# Sheet1.net
KiCad netlist of a schematic drawn in Altium Designer
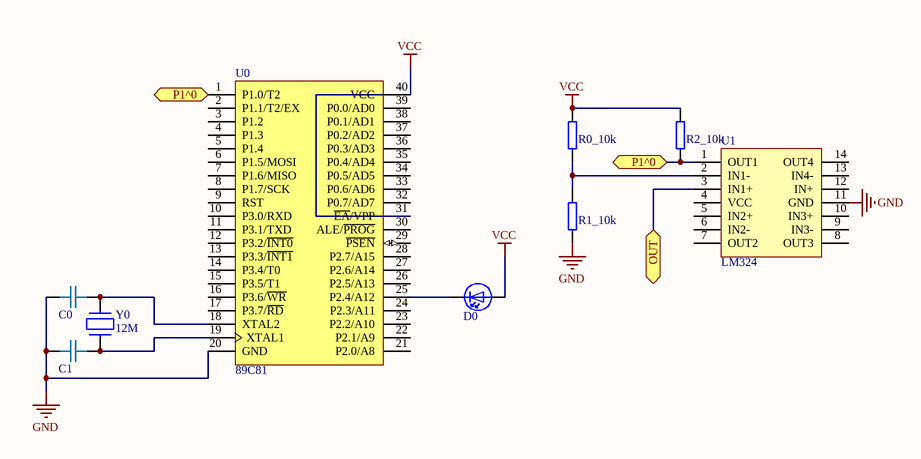
[diagram p0: Sheet1.SchDoc]

(export (version "E")
  (design (tool "Eeschema 10.0.6"))
  (components
    (comp (ref "C0") (value "22pf") (footprint "capacitor-0.1") (libsource (lib "单片机常用原件库") (part "C_1")))
    (comp (ref "C1") (value "C_1") (footprint "capacitor-0.1") (libsource (lib "单片机常用原件库") (part "C_1")))
    (comp (ref "D0") (value "LED") (footprint "led-3") (libsource (lib "单片机常用原件库") (part "LED-30")))
    (comp (ref "R0_10k")
      (value "RESIS")
      (footprint "resistor-0.4")
      (libsource (lib "单片机常用原件库") (part "RESIS"))
    )
    (comp (ref "R1_10k")
      (value "RESIS")
      (footprint "resistor-0.4")
      (libsource (lib "单片机常用原件库") (part "RESIS"))
    )
    (comp (ref "R2_10k")
      (value "RESIS")
      (footprint "resistor-0.4")
      (libsource (lib "单片机常用原件库") (part "RESIS"))
    )
    (comp (ref "U0")
      (value "89C81")
      (footprint "STC12C5A08S2")
      (libsource (lib "单片机常用原件库") (part "STC12C5A08S2"))
    )
    (comp (ref "U1") (value "LM324") (footprint "DIP14") (libsource (lib "单片机常用原件库") (part "LM324")))
    (comp (ref "Y0")
      (value "XTAL")
      (footprint "Axial 0.2")
      (fields (field (name "ALTIUM_UNNAMED_1") "12M"))
      (libsource (lib "单片机常用原件库") (part "XTAL"))
    )
  )
  (nets
    (net (code "1") (name "/OUT") (class "Default")
      (node (ref "U1") (pin "3") (pinfunction "IN1+_3") (pintype "passive"))
    )
    (net (code "2") (name "/P1^0") (class "Default")
      (node (ref "R2_10k") (pin "1") (pinfunction "1_1") (pintype "passive"))
      (node (ref "U0") (pin "1") (pinfunction "P1.0/T2_1") (pintype "passive"))
      (node (ref "U1") (pin "1") (pinfunction "OUT1_1") (pintype "passive"))
    )
    (net (code "3") (name "GND") (class "Default")
      (node (ref "C0") (pin "1") (pinfunction "1_1") (pintype "passive"))
      (node (ref "C1") (pin "1") (pinfunction "1_1") (pintype "passive"))
      (node (ref "R1_10k") (pin "1") (pinfunction "1_1") (pintype "passive"))
      (node (ref "U0") (pin "20") (pinfunction "GND_20") (pintype "passive"))
      (node (ref "U1") (pin "11") (pinfunction "GND_11") (pintype "passive"))
    )
    (net (code "4") (name "Net-(U0-P2.4{slash}A12)") (class "Default")
      (node (ref "D0") (pin "2") (pintype "passive"))
      (node (ref "U0") (pin "25") (pinfunction "P2.4/A12_25") (pintype "passive"))
    )
    (net (code "5") (name "Net-(U0-XTAL1)") (class "Default")
      (node (ref "C1") (pin "2") (pinfunction "2_2") (pintype "passive"))
      (node (ref "U0") (pin "19") (pinfunction "XTAL1_19") (pintype "passive"))
      (node (ref "Y0") (pin "1") (pinfunction "1_1") (pintype "passive"))
    )
    (net (code "6") (name "Net-(U0-XTAL2)") (class "Default")
      (node (ref "C0") (pin "2") (pinfunction "2_2") (pintype "passive"))
      (node (ref "U0") (pin "18") (pinfunction "XTAL2_18") (pintype "passive"))
      (node (ref "Y0") (pin "2") (pinfunction "2_2") (pintype "passive"))
    )
    (net (code "7") (name "Net-(U1-IN1-)") (class "Default")
      (node (ref "R0_10k") (pin "1") (pinfunction "1_1") (pintype "passive"))
      (node (ref "R1_10k") (pin "2") (pinfunction "2_2") (pintype "passive"))
      (node (ref "U1") (pin "2") (pinfunction "IN1-_2") (pintype "passive"))
    )
    (net (code "8") (name "VCC") (class "Default")
      (node (ref "D0") (pin "1") (pintype "passive"))
      (node (ref "R0_10k") (pin "2") (pinfunction "2_2") (pintype "passive"))
      (node (ref "R2_10k") (pin "2") (pinfunction "2_2") (pintype "passive"))
      (node (ref "U0") (pin "40") (pinfunction "VCC_40") (pintype "passive"))
    )
    (net (code "9") (name "unconnected-(U0-ALE{slash}~{PROG}-Pad30)") (class "Default")
      (node (ref "U0") (pin "30") (pinfunction "ALE/~{PROG}_30") (pintype "passive"))
    )
    (net (code "10") (name "unconnected-(U0-P0.0{slash}AD0-Pad39)") (class "Default")
      (node (ref "U0") (pin "39") (pinfunction "P0.0/AD0_39") (pintype "passive"))
    )
    (net (code "11") (name "unconnected-(U0-P0.1{slash}AD1-Pad38)") (class "Default")
      (node (ref "U0") (pin "38") (pinfunction "P0.1/AD1_38") (pintype "passive"))
    )
    (net (code "12") (name "unconnected-(U0-P0.2{slash}AD2-Pad37)") (class "Default")
      (node (ref "U0") (pin "37") (pinfunction "P0.2/AD2_37") (pintype "passive"))
    )
    (net (code "13") (name "unconnected-(U0-P0.3{slash}AD3-Pad36)") (class "Default")
      (node (ref "U0") (pin "36") (pinfunction "P0.3/AD3_36") (pintype "passive"))
    )
    (net (code "14") (name "unconnected-(U0-P0.4{slash}AD4-Pad35)") (class "Default")
      (node (ref "U0") (pin "35") (pinfunction "P0.4/AD4_35") (pintype "passive"))
    )
    (net (code "15") (name "unconnected-(U0-P0.5{slash}AD5-Pad34)") (class "Default")
      (node (ref "U0") (pin "34") (pinfunction "P0.5/AD5_34") (pintype "passive"))
    )
    (net (code "16") (name "unconnected-(U0-P0.6{slash}AD6-Pad33)") (class "Default")
      (node (ref "U0") (pin "33") (pinfunction "P0.6/AD6_33") (pintype "passive"))
    )
    (net (code "17") (name "unconnected-(U0-P0.7{slash}AD7-Pad32)") (class "Default")
      (node (ref "U0") (pin "32") (pinfunction "P0.7/AD7_32") (pintype "passive"))
    )
    (net (code "18") (name "unconnected-(U0-P1.1{slash}T2{slash}EX-Pad2)") (class "Default")
      (node (ref "U0") (pin "2") (pinfunction "P1.1/T2/EX_2") (pintype "passive"))
    )
    (net (code "19") (name "unconnected-(U0-P1.2-Pad3)") (class "Default")
      (node (ref "U0") (pin "3") (pinfunction "P1.2_3") (pintype "passive"))
    )
    (net (code "20") (name "unconnected-(U0-P1.3-Pad4)") (class "Default")
      (node (ref "U0") (pin "4") (pinfunction "P1.3_4") (pintype "passive"))
    )
    (net (code "21") (name "unconnected-(U0-P1.4-Pad5)") (class "Default")
      (node (ref "U0") (pin "5") (pinfunction "P1.4_5") (pintype "passive"))
    )
    (net (code "22") (name "unconnected-(U0-P1.5{slash}MOSI-Pad6)") (class "Default")
      (node (ref "U0") (pin "6") (pinfunction "P1.5/MOSI_6") (pintype "passive"))
    )
    (net (code "23") (name "unconnected-(U0-P1.6{slash}MISO-Pad7)") (class "Default")
      (node (ref "U0") (pin "7") (pinfunction "P1.6/MISO_7") (pintype "passive"))
    )
    (net (code "24") (name "unconnected-(U0-P1.7{slash}SCK-Pad8)") (class "Default")
      (node (ref "U0") (pin "8") (pinfunction "P1.7/SCK_8") (pintype "passive"))
    )
    (net (code "25") (name "unconnected-(U0-P2.0{slash}A8-Pad21)") (class "Default")
      (node (ref "U0") (pin "21") (pinfunction "P2.0/A8_21") (pintype "passive"))
    )
    (net (code "26") (name "unconnected-(U0-P2.1{slash}A9-Pad22)") (class "Default")
      (node (ref "U0") (pin "22") (pinfunction "P2.1/A9_22") (pintype "passive"))
    )
    (net (code "27") (name "unconnected-(U0-P2.2{slash}A10-Pad23)") (class "Default")
      (node (ref "U0") (pin "23") (pinfunction "P2.2/A10_23") (pintype "passive"))
    )
    (net (code "28") (name "unconnected-(U0-P2.3{slash}A11-Pad24)") (class "Default")
      (node (ref "U0") (pin "24") (pinfunction "P2.3/A11_24") (pintype "passive"))
    )
    (net (code "29") (name "unconnected-(U0-P2.5{slash}A13-Pad26)") (class "Default")
      (node (ref "U0") (pin "26") (pinfunction "P2.5/A13_26") (pintype "passive"))
    )
    (net (code "30") (name "unconnected-(U0-P2.6{slash}A14-Pad27)") (class "Default")
      (node (ref "U0") (pin "27") (pinfunction "P2.6/A14_27") (pintype "passive"))
    )
    (net (code "31") (name "unconnected-(U0-P2.7{slash}A15-Pad28)") (class "Default")
      (node (ref "U0") (pin "28") (pinfunction "P2.7/A15_28") (pintype "passive"))
    )
    (net (code "32") (name "unconnected-(U0-P3.0{slash}RXD-Pad10)") (class "Default")
      (node (ref "U0") (pin "10") (pinfunction "P3.0/RXD_10") (pintype "passive"))
    )
    (net (code "33") (name "unconnected-(U0-P3.1{slash}TXD-Pad11)") (class "Default")
      (node (ref "U0") (pin "11") (pinfunction "P3.1/TXD_11") (pintype "passive"))
    )
    (net (code "34") (name "unconnected-(U0-P3.2{slash}~{INT0}-Pad12)") (class "Default")
      (node (ref "U0") (pin "12") (pinfunction "P3.2/~{INT0}_12") (pintype "passive"))
    )
    (net (code "35") (name "unconnected-(U0-P3.3{slash}~{INT1}-Pad13)") (class "Default")
      (node (ref "U0") (pin "13") (pinfunction "P3.3/~{INT1}_13") (pintype "passive"))
    )
    (net (code "36") (name "unconnected-(U0-P3.4{slash}T0-Pad14)") (class "Default")
      (node (ref "U0") (pin "14") (pinfunction "P3.4/T0_14") (pintype "passive"))
    )
    (net (code "37") (name "unconnected-(U0-P3.5{slash}T1-Pad15)") (class "Default")
      (node (ref "U0") (pin "15") (pinfunction "P3.5/T1_15") (pintype "passive"))
    )
    (net (code "38") (name "unconnected-(U0-P3.6{slash}~{WR}-Pad16)") (class "Default")
      (node (ref "U0") (pin "16") (pinfunction "P3.6/~{WR}_16") (pintype "passive"))
    )
    (net (code "39") (name "unconnected-(U0-P3.7{slash}~{RD}-Pad17)") (class "Default")
      (node (ref "U0") (pin "17") (pinfunction "P3.7/~{RD}_17") (pintype "passive"))
    )
    (net (code "40") (name "unconnected-(U0-RST-Pad9)") (class "Default")
      (node (ref "U0") (pin "9") (pinfunction "RST_9") (pintype "passive"))
    )
    (net (code "41") (name "unconnected-(U0-~{EA}{slash}VPP-Pad31)") (class "Default")
      (node (ref "U0") (pin "31") (pinfunction "~{EA}/VPP_31") (pintype "passive"))
    )
    (net (code "42") (name "unconnected-(U0-~{PSEN}-Pad29)") (class "Default")
      (node (ref "U0") (pin "29") (pinfunction "~{PSEN}_29") (pintype "bidirectional"))
    )
    (net (code "43") (name "unconnected-(U1-IN+-Pad12)") (class "Default")
      (node (ref "U1") (pin "12") (pinfunction "IN+_12") (pintype "passive"))
    )
    (net (code "44") (name "unconnected-(U1-IN2+-Pad5)") (class "Default")
      (node (ref "U1") (pin "5") (pinfunction "IN2+_5") (pintype "passive"))
    )
    (net (code "45") (name "unconnected-(U1-IN2--Pad6)") (class "Default")
      (node (ref "U1") (pin "6") (pinfunction "IN2-_6") (pintype "passive"))
    )
    (net (code "46") (name "unconnected-(U1-IN3+-Pad10)") (class "Default")
      (node (ref "U1") (pin "10") (pinfunction "IN3+_10") (pintype "passive"))
    )
    (net (code "47") (name "unconnected-(U1-IN3--Pad9)") (class "Default")
      (node (ref "U1") (pin "9") (pinfunction "IN3-_9") (pintype "passive"))
    )
    (net (code "48") (name "unconnected-(U1-IN4--Pad13)") (class "Default")
      (node (ref "U1") (pin "13") (pinfunction "IN4-_13") (pintype "passive"))
    )
    (net (code "49") (name "unconnected-(U1-OUT2-Pad7)") (class "Default")
      (node (ref "U1") (pin "7") (pinfunction "OUT2_7") (pintype "passive"))
    )
    (net (code "50") (name "unconnected-(U1-OUT3-Pad8)") (class "Default")
      (node (ref "U1") (pin "8") (pinfunction "OUT3_8") (pintype "passive"))
    )
    (net (code "51") (name "unconnected-(U1-OUT4-Pad14)") (class "Default")
      (node (ref "U1") (pin "14") (pinfunction "OUT4_14") (pintype "passive"))
    )
    (net (code "52") (name "unconnected-(U1-VCC-Pad4)") (class "Default")
      (node (ref "U1") (pin "4") (pinfunction "VCC_4") (pintype "passive"))
    )
  )
)
